# Shield.net
KiCad netlist of a schematic drawn in EAGLE
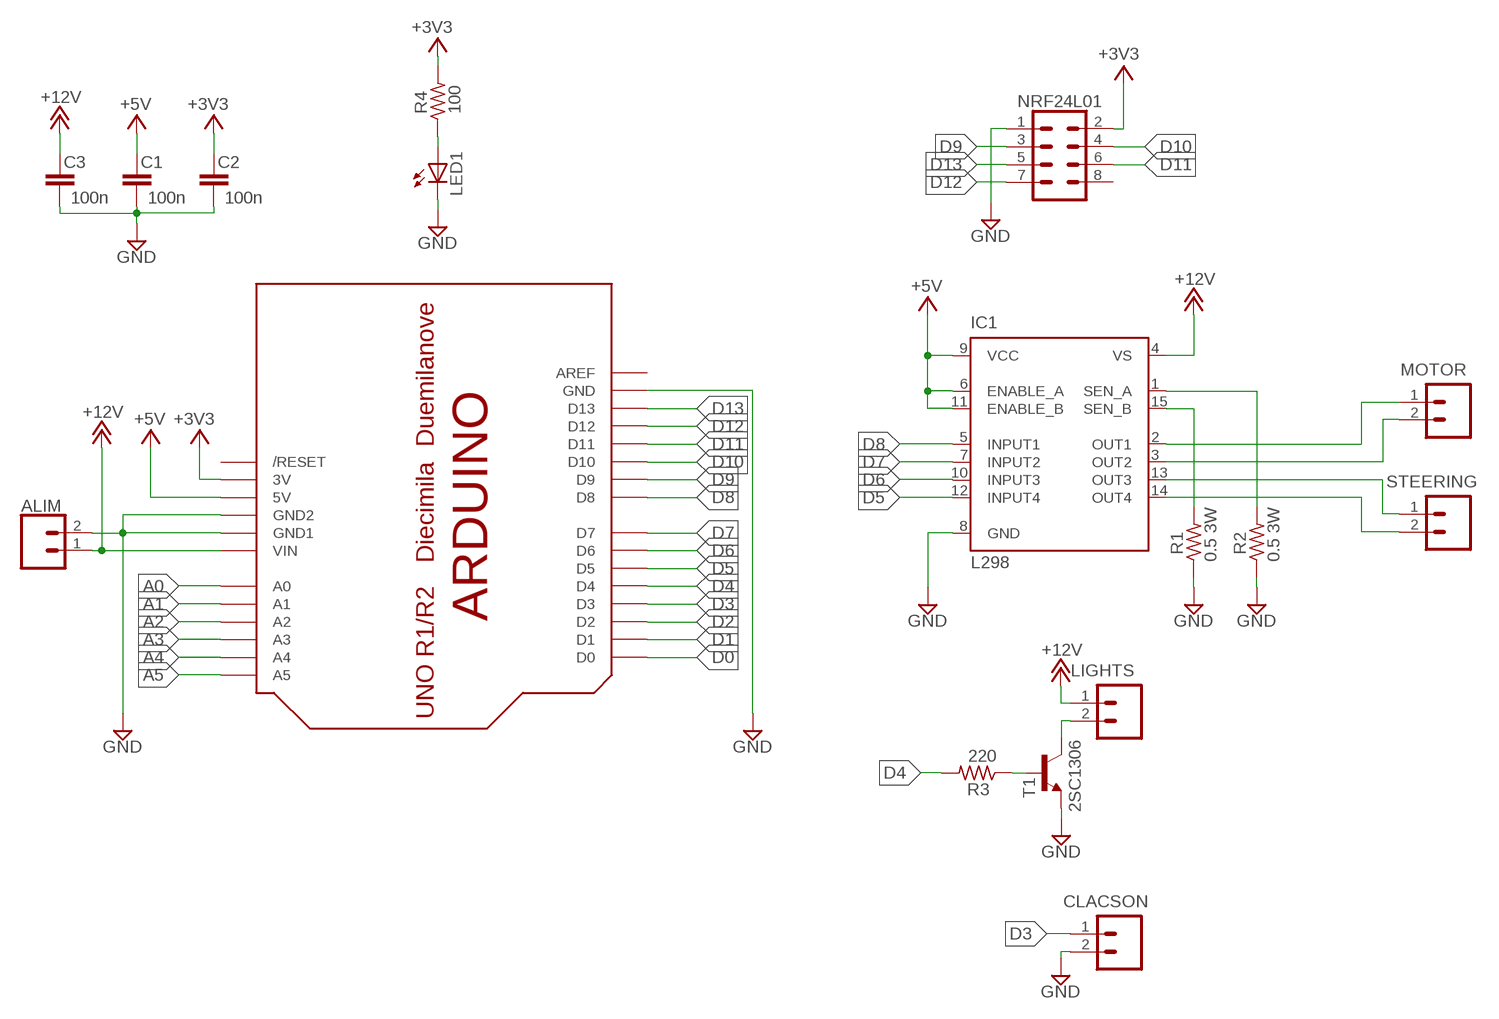
[diagram p0: schematic, sheet 1]

(export (version "E")
  (design (tool "Eeschema 10.0.6"))
  (components
    (comp (ref "ALIM")
      (value "CONN_025MM")
      (footprint "eagle-import:SCREWTERMINAL-5MM-2")
      (libsource (lib "eagle-import") (part "CONN_025MM"))
    )
    (comp (ref "C1")
      (value "100n")
      (footprint "eagle-import:C5B2.5")
      (libsource (lib "eagle-import") (part "C5/2.5"))
    )
    (comp (ref "C2")
      (value "100n")
      (footprint "eagle-import:C5B2.5")
      (libsource (lib "eagle-import") (part "C5/2.5"))
    )
    (comp (ref "C3")
      (value "100n")
      (footprint "eagle-import:C5B2.5")
      (libsource (lib "eagle-import") (part "C5/2.5"))
    )
    (comp (ref "CLACSON")
      (value "CONN_025MM")
      (footprint "eagle-import:SCREWTERMINAL-5MM-2")
      (libsource (lib "eagle-import") (part "CONN_025MM"))
    )
    (comp (ref "IC1")
      (value "L298")
      (footprint "eagle-import:MULTIWATT-15")
      (fields (field (name "MPN") "L298N"))
      (libsource (lib "eagle-import") (part "L298"))
    )
    (comp (ref "LED1")
      (value "LED5MM")
      (footprint "eagle-import:LED5MM")
      (libsource (lib "eagle-import") (part "LED5MM"))
    )
    (comp (ref "LIGHTS")
      (value "CONN_025MM")
      (footprint "eagle-import:SCREWTERMINAL-5MM-2")
      (libsource (lib "eagle-import") (part "CONN_025MM"))
    )
    (comp (ref "MOTOR")
      (value "CONN_025MM")
      (footprint "eagle-import:SCREWTERMINAL-5MM-2")
      (libsource (lib "eagle-import") (part "CONN_025MM"))
    )
    (comp (ref "NRF24L01")
      (value "CONN_04X2")
      (footprint "eagle-import:2X4")
      (libsource (lib "eagle-import") (part "CONN_04X2"))
    )
    (comp (ref "R1")
      (value "0.5 3W")
      (footprint "eagle-import:0309_12")
      (libsource (lib "eagle-import") (part "R-US_0309/12"))
    )
    (comp (ref "R2")
      (value "0.5 3W")
      (footprint "eagle-import:0309_12")
      (libsource (lib "eagle-import") (part "R-US_0309/12"))
    )
    (comp (ref "R3")
      (value "220")
      (footprint "eagle-import:0309_12")
      (libsource (lib "eagle-import") (part "R-US_0309/12"))
    )
    (comp (ref "R4")
      (value "100")
      (footprint "eagle-import:0309_12")
      (libsource (lib "eagle-import") (part "R-US_0309/12"))
    )
    (comp (ref "STEERING")
      (value "CONN_025MM")
      (footprint "eagle-import:SCREWTERMINAL-5MM-2")
      (libsource (lib "eagle-import") (part "CONN_025MM"))
    )
    (comp (ref "T1")
      (value "2SC1306")
      (footprint "eagle-import:TO220BV")
      (libsource (lib "eagle-import") (part "2SC1306"))
    )
    (comp (ref "U$1")
      (value "ARDUINO-NOHOLE")
      (footprint "eagle-import:ARDUINO-NOHOLE")
      (libsource (lib "eagle-import") (part "ARDUINO-NOHOLE"))
    )
  )
  (nets
    (net (code "1") (name "+3V3") (class "Default")
      (node (ref "C2") (pin "1") (pinfunction "1_1") (pintype "passive"))
      (node (ref "NRF24L01") (pin "2") (pinfunction "2_2") (pintype "passive"))
      (node (ref "R4") (pin "2") (pinfunction "2_2") (pintype "passive"))
      (node (ref "U$1") (pin "3V") (pinfunction "3V_3V") (pintype "power_in"))
    )
    (net (code "2") (name "+5V") (class "Default")
      (node (ref "C1") (pin "1") (pinfunction "1_1") (pintype "passive"))
      (node (ref "IC1") (pin "11") (pinfunction "ENABLE_B_11") (pintype "input"))
      (node (ref "IC1") (pin "6") (pinfunction "ENABLE_A_6") (pintype "input"))
      (node (ref "IC1") (pin "9") (pinfunction "VCC_9") (pintype "power_in"))
      (node (ref "U$1") (pin "5V") (pinfunction "5V_5V") (pintype "power_in"))
    )
    (net (code "3") (name "+12V") (class "Default")
      (node (ref "ALIM") (pin "1") (pinfunction "1_1") (pintype "passive"))
      (node (ref "C3") (pin "1") (pinfunction "1_1") (pintype "passive"))
      (node (ref "IC1") (pin "4") (pinfunction "VS_4") (pintype "power_in"))
      (node (ref "LIGHTS") (pin "1") (pinfunction "1_1") (pintype "passive"))
      (node (ref "U$1") (pin "VIN") (pinfunction "VIN_VIN") (pintype "power_in"))
    )
    (net (code "4") (name "A0") (class "Default")
      (node (ref "U$1") (pin "A0") (pinfunction "A0_A0") (pintype "bidirectional"))
    )
    (net (code "5") (name "A1") (class "Default")
      (node (ref "U$1") (pin "A1") (pinfunction "A1_A1") (pintype "bidirectional"))
    )
    (net (code "6") (name "A2") (class "Default")
      (node (ref "U$1") (pin "A2") (pinfunction "A2_A2") (pintype "bidirectional"))
    )
    (net (code "7") (name "A3") (class "Default")
      (node (ref "U$1") (pin "A3") (pinfunction "A3_A3") (pintype "bidirectional"))
    )
    (net (code "8") (name "A4") (class "Default")
      (node (ref "U$1") (pin "A4") (pinfunction "A4_A4") (pintype "bidirectional"))
    )
    (net (code "9") (name "A5") (class "Default")
      (node (ref "U$1") (pin "A5") (pinfunction "A5_A5") (pintype "bidirectional"))
    )
    (net (code "10") (name "D0") (class "Default")
      (node (ref "U$1") (pin "D0") (pinfunction "D0_D0") (pintype "bidirectional"))
    )
    (net (code "11") (name "D1") (class "Default")
      (node (ref "U$1") (pin "D1") (pinfunction "D1_D1") (pintype "bidirectional"))
    )
    (net (code "12") (name "D2") (class "Default")
      (node (ref "U$1") (pin "D2") (pinfunction "D2_D2") (pintype "bidirectional"))
    )
    (net (code "13") (name "D3") (class "Default")
      (node (ref "CLACSON") (pin "1") (pinfunction "1_1") (pintype "passive"))
      (node (ref "U$1") (pin "D3") (pinfunction "D3_D3") (pintype "bidirectional"))
    )
    (net (code "14") (name "D4") (class "Default")
      (node (ref "R3") (pin "2") (pinfunction "2_2") (pintype "passive"))
      (node (ref "U$1") (pin "D4") (pinfunction "D4_D4") (pintype "bidirectional"))
    )
    (net (code "15") (name "D5") (class "Default")
      (node (ref "IC1") (pin "12") (pinfunction "INPUT4_12") (pintype "input"))
      (node (ref "U$1") (pin "D5") (pinfunction "D5_D5") (pintype "bidirectional"))
    )
    (net (code "16") (name "D6") (class "Default")
      (node (ref "IC1") (pin "10") (pinfunction "INPUT3_10") (pintype "input"))
      (node (ref "U$1") (pin "D6") (pinfunction "D6_D6") (pintype "bidirectional"))
    )
    (net (code "17") (name "D7") (class "Default")
      (node (ref "IC1") (pin "7") (pinfunction "INPUT2_7") (pintype "input"))
      (node (ref "U$1") (pin "D7") (pinfunction "D7_D7") (pintype "bidirectional"))
    )
    (net (code "18") (name "D8") (class "Default")
      (node (ref "IC1") (pin "5") (pinfunction "INPUT1_5") (pintype "input"))
      (node (ref "U$1") (pin "D8") (pinfunction "D8_D8") (pintype "bidirectional"))
    )
    (net (code "19") (name "D9") (class "Default")
      (node (ref "NRF24L01") (pin "3") (pinfunction "3_3") (pintype "passive"))
      (node (ref "U$1") (pin "D9") (pinfunction "D9_D9") (pintype "bidirectional"))
    )
    (net (code "20") (name "D10") (class "Default")
      (node (ref "NRF24L01") (pin "4") (pinfunction "4_4") (pintype "passive"))
      (node (ref "U$1") (pin "D10") (pinfunction "D10_D10") (pintype "bidirectional"))
    )
    (net (code "21") (name "D11") (class "Default")
      (node (ref "NRF24L01") (pin "6") (pinfunction "6_6") (pintype "passive"))
      (node (ref "U$1") (pin "D11") (pinfunction "D11_D11") (pintype "bidirectional"))
    )
    (net (code "22") (name "D12") (class "Default")
      (node (ref "NRF24L01") (pin "7") (pinfunction "7_7") (pintype "passive"))
      (node (ref "U$1") (pin "D12") (pinfunction "D12_D12") (pintype "bidirectional"))
    )
    (net (code "23") (name "D13") (class "Default")
      (node (ref "NRF24L01") (pin "5") (pinfunction "5_5") (pintype "passive"))
      (node (ref "U$1") (pin "D13") (pinfunction "D13_D13") (pintype "bidirectional"))
    )
    (net (code "24") (name "GND") (class "Default")
      (node (ref "ALIM") (pin "2") (pinfunction "2_2") (pintype "passive"))
      (node (ref "C1") (pin "2") (pinfunction "2_2") (pintype "passive"))
      (node (ref "C2") (pin "2") (pinfunction "2_2") (pintype "passive"))
      (node (ref "C3") (pin "2") (pinfunction "2_2") (pintype "passive"))
      (node (ref "CLACSON") (pin "2") (pinfunction "2_2") (pintype "passive"))
      (node (ref "IC1") (pin "8") (pinfunction "GND_8") (pintype "power_in"))
      (node (ref "LED1") (pin "K") (pinfunction "C_K") (pintype "passive"))
      (node (ref "NRF24L01") (pin "1") (pinfunction "1_1") (pintype "passive"))
      (node (ref "R1") (pin "1") (pinfunction "1_1") (pintype "passive"))
      (node (ref "R2") (pin "1") (pinfunction "1_1") (pintype "passive"))
      (node (ref "T1") (pin "3") (pinfunction "E_3") (pintype "passive"))
      (node (ref "U$1") (pin "GND") (pinfunction "GND_GND") (pintype "power_in"))
      (node (ref "U$1") (pin "GND1") (pinfunction "GND1_GND1") (pintype "power_in"))
      (node (ref "U$1") (pin "GND2") (pinfunction "GND2_GND2") (pintype "power_in"))
    )
    (net (code "25") (name "Net-(IC1-OUT1)") (class "Default")
      (node (ref "IC1") (pin "2") (pinfunction "OUT1_2") (pintype "output"))
      (node (ref "MOTOR") (pin "1") (pinfunction "1_1") (pintype "passive"))
    )
    (net (code "26") (name "Net-(IC1-OUT2)") (class "Default")
      (node (ref "IC1") (pin "3") (pinfunction "OUT2_3") (pintype "output"))
      (node (ref "MOTOR") (pin "2") (pinfunction "2_2") (pintype "passive"))
    )
    (net (code "27") (name "Net-(IC1-OUT3)") (class "Default")
      (node (ref "IC1") (pin "13") (pinfunction "OUT3_13") (pintype "output"))
      (node (ref "STEERING") (pin "1") (pinfunction "1_1") (pintype "passive"))
    )
    (net (code "28") (name "Net-(IC1-OUT4)") (class "Default")
      (node (ref "IC1") (pin "14") (pinfunction "OUT4_14") (pintype "output"))
      (node (ref "STEERING") (pin "2") (pinfunction "2_2") (pintype "passive"))
    )
    (net (code "29") (name "Net-(IC1-SEN_A)") (class "Default")
      (node (ref "IC1") (pin "1") (pinfunction "SEN_A_1") (pintype "input"))
      (node (ref "R2") (pin "2") (pinfunction "2_2") (pintype "passive"))
    )
    (net (code "30") (name "Net-(IC1-SEN_B)") (class "Default")
      (node (ref "IC1") (pin "15") (pinfunction "SEN_B_15") (pintype "input"))
      (node (ref "R1") (pin "2") (pinfunction "2_2") (pintype "passive"))
    )
    (net (code "31") (name "Net-(LED1-PadA)") (class "Default")
      (node (ref "LED1") (pin "A") (pinfunction "A_A") (pintype "passive"))
      (node (ref "R4") (pin "1") (pinfunction "1_1") (pintype "passive"))
    )
    (net (code "32") (name "Net-(T1-B)") (class "Default")
      (node (ref "R3") (pin "1") (pinfunction "1_1") (pintype "passive"))
      (node (ref "T1") (pin "1") (pinfunction "B_1") (pintype "passive"))
    )
    (net (code "33") (name "Net-(T1-C)") (class "Default")
      (node (ref "LIGHTS") (pin "2") (pinfunction "2_2") (pintype "passive"))
      (node (ref "T1") (pin "2") (pinfunction "C_2") (pintype "passive"))
    )
    (net (code "34") (name "unconnected-(NRF24L01-Pad8)") (class "Default")
      (node (ref "NRF24L01") (pin "8") (pinfunction "8_8") (pintype "passive"))
    )
    (net (code "35") (name "unconnected-(U$1-PadAREF)") (class "Default")
      (node (ref "U$1") (pin "AREF") (pinfunction "AREF_AREF") (pintype "bidirectional"))
    )
    (net (code "36") (name "unconnected-(U$1-{slash}RESET-PadRESET)") (class "Default")
      (node (ref "U$1") (pin "RESET") (pinfunction "/RESET_RESET") (pintype "bidirectional"))
    )
  )
)
